# placa_TC.net
KiCad netlist of a schematic drawn in EAGLE
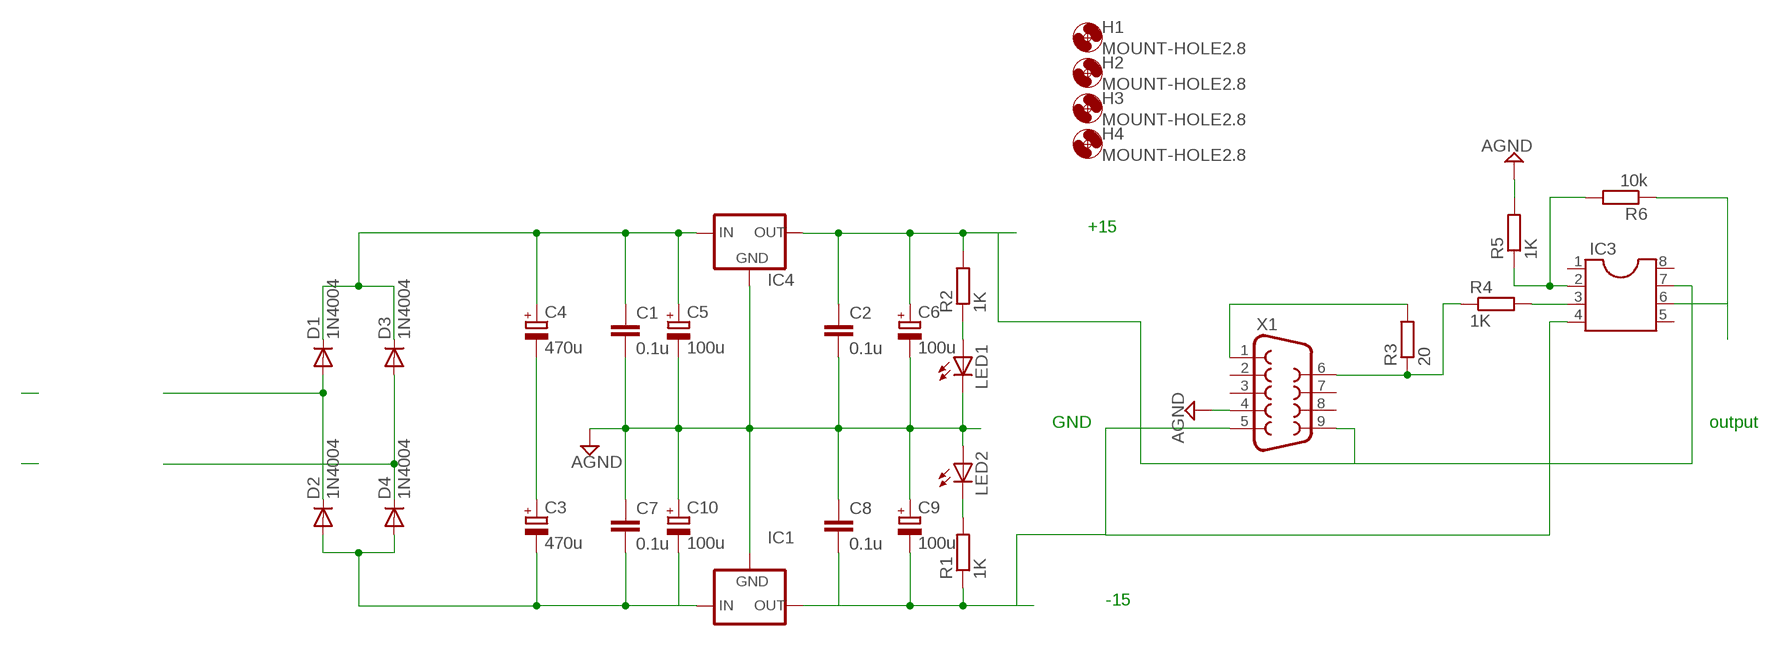
[diagram p0: schematic, sheet 1]

(export (version "E")
  (design (tool "Eeschema 10.0.6"))
  (components
    (comp (ref "C1")
      (value "0.1u")
      (footprint "eagle-import:C025-024X044")
      (libsource (lib "eagle-import") (part "C-EU025-024X044"))
    )
    (comp (ref "C2")
      (value "0.1u")
      (footprint "eagle-import:C025-024X044")
      (libsource (lib "eagle-import") (part "C-EU025-024X044"))
    )
    (comp (ref "C3")
      (value "470u")
      (footprint "eagle-import:E5-10,5")
      (libsource (lib "eagle-import") (part "CPOL-EUE5-10.5"))
    )
    (comp (ref "C4")
      (value "470u")
      (footprint "eagle-import:E5-10,5")
      (libsource (lib "eagle-import") (part "CPOL-EUE5-10.5"))
    )
    (comp (ref "C5")
      (value "100u")
      (footprint "eagle-import:E5-10,5")
      (libsource (lib "eagle-import") (part "CPOL-EUE5-10.5"))
    )
    (comp (ref "C6")
      (value "100u")
      (footprint "eagle-import:E5-10,5")
      (libsource (lib "eagle-import") (part "CPOL-EUE5-10.5"))
    )
    (comp (ref "C7")
      (value "0.1u")
      (footprint "eagle-import:C025-024X044")
      (libsource (lib "eagle-import") (part "C-EU025-024X044"))
    )
    (comp (ref "C8")
      (value "0.1u")
      (footprint "eagle-import:C025-024X044")
      (libsource (lib "eagle-import") (part "C-EU025-024X044"))
    )
    (comp (ref "C9")
      (value "100u")
      (footprint "eagle-import:E5-10,5")
      (libsource (lib "eagle-import") (part "CPOL-EUE5-10.5"))
    )
    (comp (ref "C10")
      (value "100u")
      (footprint "eagle-import:E5-10,5")
      (libsource (lib "eagle-import") (part "CPOL-EUE5-10.5"))
    )
    (comp (ref "D1")
      (value "1N4004")
      (footprint "eagle-import:DO41-10")
      (libsource (lib "eagle-import") (part "1N4004"))
    )
    (comp (ref "D2")
      (value "1N4004")
      (footprint "eagle-import:DO41-10")
      (libsource (lib "eagle-import") (part "1N4004"))
    )
    (comp (ref "D3")
      (value "1N4004")
      (footprint "eagle-import:DO41-10")
      (libsource (lib "eagle-import") (part "1N4004"))
    )
    (comp (ref "D4")
      (value "1N4004")
      (footprint "eagle-import:DO41-10")
      (libsource (lib "eagle-import") (part "1N4004"))
    )
    (comp (ref "H1")
      (value "MOUNT-HOLE2.8")
      (footprint "eagle-import:2,8")
      (libsource (lib "eagle-import") (part "MOUNT-HOLE2.8"))
    )
    (comp (ref "H2")
      (value "MOUNT-HOLE2.8")
      (footprint "eagle-import:2,8")
      (libsource (lib "eagle-import") (part "MOUNT-HOLE2.8"))
    )
    (comp (ref "H3")
      (value "MOUNT-HOLE2.8")
      (footprint "eagle-import:2,8")
      (libsource (lib "eagle-import") (part "MOUNT-HOLE2.8"))
    )
    (comp (ref "H4")
      (value "MOUNT-HOLE2.8")
      (footprint "eagle-import:2,8")
      (libsource (lib "eagle-import") (part "MOUNT-HOLE2.8"))
    )
    (comp (ref "IC1")
      (value "79XXS")
      (footprint "eagle-import:79XXS")
      (libsource (lib "eagle-import") (part "79XXS"))
    )
    (comp (ref "IC3")
      (value "DIL8")
      (footprint "eagle-import:DIL08")
      (libsource (lib "eagle-import") (part "DIL8"))
    )
    (comp (ref "IC4")
      (value "78XXS")
      (footprint "eagle-import:78XXS")
      (libsource (lib "eagle-import") (part "78XXS"))
    )
    (comp (ref "LED1")
      (value "LED3MM")
      (footprint "eagle-import:LED3MM")
      (libsource (lib "eagle-import") (part "LED3MM"))
    )
    (comp (ref "LED2")
      (value "LED3MM")
      (footprint "eagle-import:LED3MM")
      (libsource (lib "eagle-import") (part "LED3MM"))
    )
    (comp (ref "R1")
      (value "1K")
      (footprint "eagle-import:0207_10")
      (libsource (lib "eagle-import") (part "R-EU_0207/10"))
    )
    (comp (ref "R2")
      (value "1K")
      (footprint "eagle-import:0207_10")
      (libsource (lib "eagle-import") (part "R-EU_0207/10"))
    )
    (comp (ref "R3")
      (value "20")
      (footprint "eagle-import:0207_10")
      (libsource (lib "eagle-import") (part "R-EU_0207/10"))
    )
    (comp (ref "R4")
      (value "1K")
      (footprint "eagle-import:0207_10")
      (libsource (lib "eagle-import") (part "R-EU_0207/10"))
    )
    (comp (ref "R5")
      (value "1K")
      (footprint "eagle-import:0207_10")
      (libsource (lib "eagle-import") (part "R-EU_0207/10"))
    )
    (comp (ref "R6")
      (value "10k")
      (footprint "eagle-import:0207_10")
      (libsource (lib "eagle-import") (part "R-EU_0207/10"))
    )
    (comp (ref "X1")
      (value "F09HP")
      (footprint "eagle-import:F09HP")
      (libsource (lib "eagle-import") (part "F09HP"))
    )
  )
  (nets
    (net (code "1") (name "AGND") (class "Default")
      (node (ref "C1") (pin "2") (pinfunction "2_2") (pintype "passive"))
      (node (ref "C10") (pin "+") (pinfunction "+_+") (pintype "passive"))
      (node (ref "C2") (pin "2") (pinfunction "2_2") (pintype "passive"))
      (node (ref "C5") (pin "-") (pinfunction "-_-") (pintype "passive"))
      (node (ref "C6") (pin "-") (pinfunction "-_-") (pintype "passive"))
      (node (ref "C7") (pin "1") (pinfunction "1_1") (pintype "passive"))
      (node (ref "C8") (pin "1") (pinfunction "1_1") (pintype "passive"))
      (node (ref "C9") (pin "+") (pinfunction "+_+") (pintype "passive"))
      (node (ref "IC1") (pin "GND") (pinfunction "GND_GND") (pintype "input"))
      (node (ref "IC4") (pin "GND") (pinfunction "GND_GND") (pintype "input"))
      (node (ref "LED1") (pin "K") (pinfunction "C_K") (pintype "passive"))
      (node (ref "LED2") (pin "A") (pinfunction "A_A") (pintype "passive"))
      (node (ref "R5") (pin "2") (pinfunction "2_2") (pintype "passive"))
      (node (ref "X1") (pin "4") (pinfunction "4_4") (pintype "passive"))
    )
    (net (code "2") (name "Net-(C1-Pad1)") (class "Default")
      (node (ref "C1") (pin "1") (pinfunction "1_1") (pintype "passive"))
      (node (ref "C4") (pin "+") (pinfunction "+_+") (pintype "passive"))
      (node (ref "C5") (pin "+") (pinfunction "+_+") (pintype "passive"))
      (node (ref "D1") (pin "C") (pinfunction "C_C") (pintype "passive"))
      (node (ref "D3") (pin "C") (pinfunction "C_C") (pintype "passive"))
      (node (ref "IC4") (pin "IN") (pinfunction "IN_IN") (pintype "input"))
    )
    (net (code "3") (name "Net-(C2-Pad1)") (class "Default")
      (node (ref "C2") (pin "1") (pinfunction "1_1") (pintype "passive"))
      (node (ref "C6") (pin "+") (pinfunction "+_+") (pintype "passive"))
      (node (ref "IC3") (pin "7") (pinfunction "7_7") (pintype "passive"))
      (node (ref "IC4") (pin "OUT") (pinfunction "OUT_OUT") (pintype "passive"))
      (node (ref "R2") (pin "2") (pinfunction "2_2") (pintype "passive"))
      (node (ref "X1") (pin "9") (pinfunction "9_9") (pintype "passive"))
    )
    (net (code "4") (name "Net-(C3-Pad+)") (class "Default")
      (node (ref "C3") (pin "+") (pinfunction "+_+") (pintype "passive"))
      (node (ref "C4") (pin "-") (pinfunction "-_-") (pintype "passive"))
    )
    (net (code "5") (name "Net-(C8-Pad2)") (class "Default")
      (node (ref "C8") (pin "2") (pinfunction "2_2") (pintype "passive"))
      (node (ref "C9") (pin "-") (pinfunction "-_-") (pintype "passive"))
      (node (ref "IC1") (pin "OUT") (pinfunction "OUT_OUT") (pintype "passive"))
      (node (ref "IC3") (pin "4") (pinfunction "4_4") (pintype "passive"))
      (node (ref "R1") (pin "1") (pinfunction "1_1") (pintype "passive"))
      (node (ref "X1") (pin "5") (pinfunction "5_5") (pintype "passive"))
    )
    (net (code "6") (name "Net-(C10-Pad-)") (class "Default")
      (node (ref "C10") (pin "-") (pinfunction "-_-") (pintype "passive"))
      (node (ref "C3") (pin "-") (pinfunction "-_-") (pintype "passive"))
      (node (ref "C7") (pin "2") (pinfunction "2_2") (pintype "passive"))
      (node (ref "D2") (pin "A") (pinfunction "A_A") (pintype "passive"))
      (node (ref "D4") (pin "A") (pinfunction "A_A") (pintype "passive"))
      (node (ref "IC1") (pin "IN") (pinfunction "IN_IN") (pintype "input"))
    )
    (net (code "7") (name "Net-(D1-PadA)") (class "Default")
      (node (ref "D1") (pin "A") (pinfunction "A_A") (pintype "passive"))
      (node (ref "D2") (pin "C") (pinfunction "C_C") (pintype "passive"))
    )
    (net (code "8") (name "Net-(D3-PadA)") (class "Default")
      (node (ref "D3") (pin "A") (pinfunction "A_A") (pintype "passive"))
      (node (ref "D4") (pin "C") (pinfunction "C_C") (pintype "passive"))
    )
    (net (code "9") (name "Net-(IC3-Pad2)") (class "Default")
      (node (ref "IC3") (pin "2") (pinfunction "2_2") (pintype "passive"))
      (node (ref "R5") (pin "1") (pinfunction "1_1") (pintype "passive"))
      (node (ref "R6") (pin "2") (pinfunction "2_2") (pintype "passive"))
    )
    (net (code "10") (name "Net-(IC3-Pad3)") (class "Default")
      (node (ref "IC3") (pin "3") (pinfunction "3_3") (pintype "passive"))
      (node (ref "R4") (pin "2") (pinfunction "2_2") (pintype "passive"))
    )
    (net (code "11") (name "Net-(IC3-Pad6)") (class "Default")
      (node (ref "IC3") (pin "6") (pinfunction "6_6") (pintype "passive"))
      (node (ref "R6") (pin "1") (pinfunction "1_1") (pintype "passive"))
    )
    (net (code "12") (name "Net-(LED1-PadA)") (class "Default")
      (node (ref "LED1") (pin "A") (pinfunction "A_A") (pintype "passive"))
      (node (ref "R2") (pin "1") (pinfunction "1_1") (pintype "passive"))
    )
    (net (code "13") (name "Net-(LED2-C)") (class "Default")
      (node (ref "LED2") (pin "K") (pinfunction "C_K") (pintype "passive"))
      (node (ref "R1") (pin "2") (pinfunction "2_2") (pintype "passive"))
    )
    (net (code "14") (name "Net-(R3-Pad1)") (class "Default")
      (node (ref "R3") (pin "1") (pinfunction "1_1") (pintype "passive"))
      (node (ref "R4") (pin "1") (pinfunction "1_1") (pintype "passive"))
      (node (ref "X1") (pin "6") (pinfunction "6_6") (pintype "passive"))
    )
    (net (code "15") (name "Net-(R3-Pad2)") (class "Default")
      (node (ref "R3") (pin "2") (pinfunction "2_2") (pintype "passive"))
      (node (ref "X1") (pin "1") (pinfunction "1_1") (pintype "passive"))
    )
    (net (code "16") (name "unconnected-(IC3-Pad1)") (class "Default")
      (node (ref "IC3") (pin "1") (pinfunction "1_1") (pintype "passive"))
    )
    (net (code "17") (name "unconnected-(IC3-Pad5)") (class "Default")
      (node (ref "IC3") (pin "5") (pinfunction "5_5") (pintype "passive"))
    )
    (net (code "18") (name "unconnected-(IC3-Pad8)") (class "Default")
      (node (ref "IC3") (pin "8") (pinfunction "8_8") (pintype "passive"))
    )
    (net (code "19") (name "unconnected-(X1-Pad2)") (class "Default")
      (node (ref "X1") (pin "2") (pinfunction "2_2") (pintype "passive"))
    )
    (net (code "20") (name "unconnected-(X1-Pad3)") (class "Default")
      (node (ref "X1") (pin "3") (pinfunction "3_3") (pintype "passive"))
    )
    (net (code "21") (name "unconnected-(X1-Pad7)") (class "Default")
      (node (ref "X1") (pin "7") (pinfunction "7_7") (pintype "passive"))
    )
    (net (code "22") (name "unconnected-(X1-Pad8)") (class "Default")
      (node (ref "X1") (pin "8") (pinfunction "8_8") (pintype "passive"))
    )
  )
)
